# elektrosluch.net
KiCad netlist of a schematic drawn in EAGLE
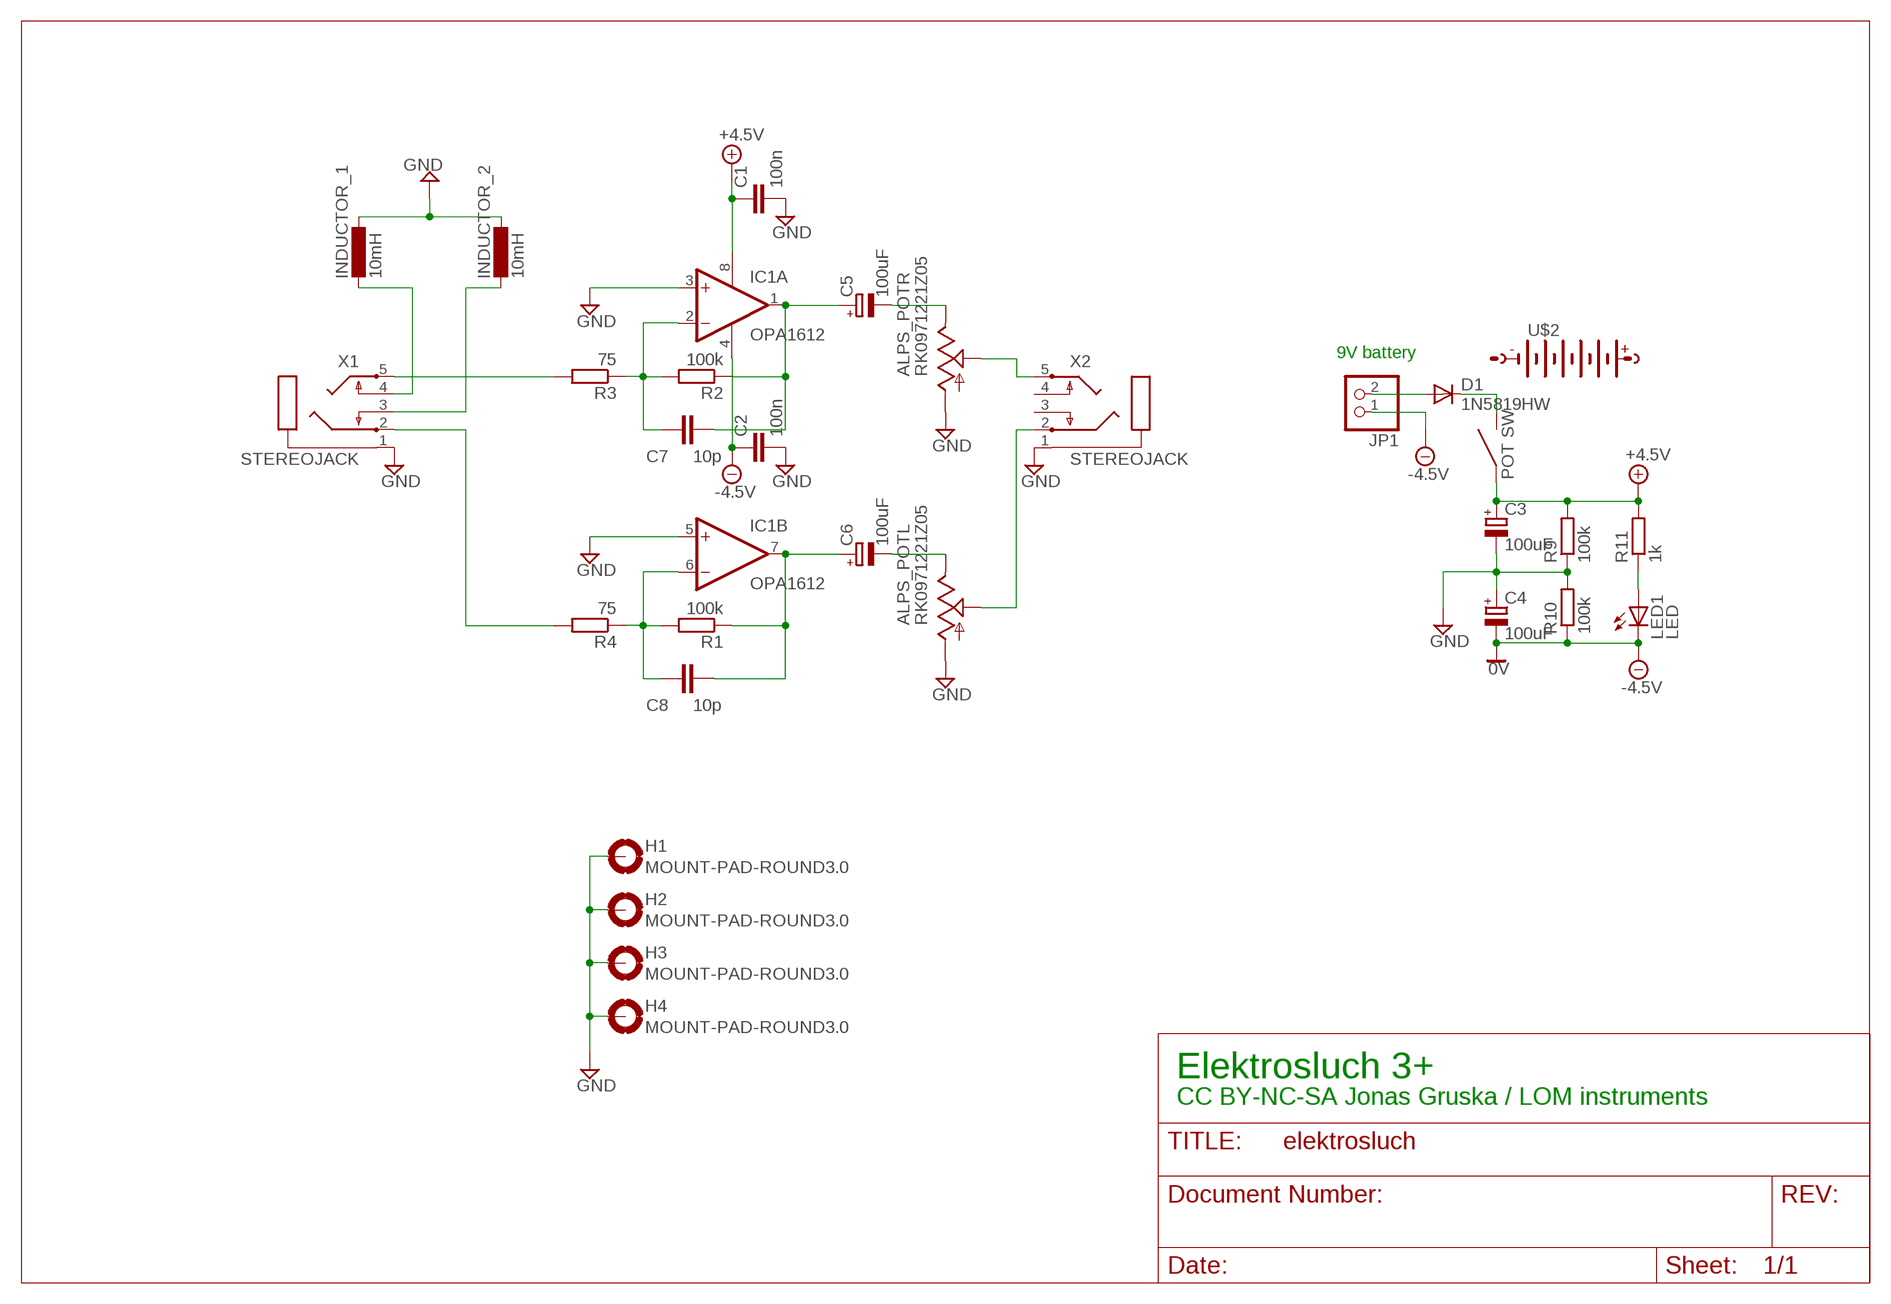
[diagram p0: schematic, sheet 1]

(export (version "E")
  (design (tool "Eeschema 10.0.6"))
  (components
    (comp (ref "ALPS_POT")
      (value "RK0971221Z05")
      (footprint "eagle-import:ALPS_RK0971221Z0X")
      (libsource (lib "eagle-import") (part "ALPS_RK0971221Z0N"))
    )
    (comp (ref "C1")
      (value "100n")
      (footprint "eagle-import:C0603")
      (libsource (lib "eagle-import") (part "C-EUC0603"))
    )
    (comp (ref "C2")
      (value "100n")
      (footprint "eagle-import:C0603")
      (libsource (lib "eagle-import") (part "C-EUC0603"))
    )
    (comp (ref "C3")
      (value "100uF")
      (footprint "eagle-import:UD-6,3X5,8_NICHICON")
      (libsource (lib "eagle-import") (part "CPOL-EUUD-6,3X8,8"))
    )
    (comp (ref "C4")
      (value "100uF")
      (footprint "eagle-import:UD-6,3X5,8_NICHICON")
      (libsource (lib "eagle-import") (part "CPOL-EUUD-6,3X8,8"))
    )
    (comp (ref "C5")
      (value "100uF")
      (footprint "eagle-import:UD-6,3X5,8_NICHICON")
      (libsource (lib "eagle-import") (part "CPOL-EUUD-6,3X8,8"))
    )
    (comp (ref "C6")
      (value "100uF")
      (footprint "eagle-import:UD-6,3X5,8_NICHICON")
      (libsource (lib "eagle-import") (part "CPOL-EUUD-6,3X8,8"))
    )
    (comp (ref "C7")
      (value "10p")
      (footprint "eagle-import:C0603")
      (libsource (lib "eagle-import") (part "C-EUC0603"))
    )
    (comp (ref "C8")
      (value "10p")
      (footprint "eagle-import:C0603")
      (libsource (lib "eagle-import") (part "C-EUC0603"))
    )
    (comp (ref "D1")
      (value "1N5819HW")
      (footprint "eagle-import:SOD123")
      (libsource (lib "eagle-import") (part "DIODE-SOD123"))
    )
    (comp (ref "H1")
      (value "MOUNT-PAD-ROUND3.0")
      (footprint "eagle-import:3,0-PAD")
      (libsource (lib "eagle-import") (part "MOUNT-PAD-ROUND3.0"))
    )
    (comp (ref "H2")
      (value "MOUNT-PAD-ROUND3.0")
      (footprint "eagle-import:3,0-PAD")
      (libsource (lib "eagle-import") (part "MOUNT-PAD-ROUND3.0"))
    )
    (comp (ref "H3")
      (value "MOUNT-PAD-ROUND3.0")
      (footprint "eagle-import:3,0-PAD")
      (libsource (lib "eagle-import") (part "MOUNT-PAD-ROUND3.0"))
    )
    (comp (ref "H4")
      (value "MOUNT-PAD-ROUND3.0")
      (footprint "eagle-import:3,0-PAD")
      (libsource (lib "eagle-import") (part "MOUNT-PAD-ROUND3.0"))
    )
    (comp (ref "IC1")
      (value "OPA1612")
      (footprint "eagle-import:SO08")
      (libsource (lib "eagle-import") (part "OPA2UA134"))
    )
    (comp (ref "INDUCTOR_1")
      (value "10mH")
      (footprint "eagle-import:COIL")
      (libsource (lib "eagle-import") (part "COIL"))
    )
    (comp (ref "INDUCTOR_2")
      (value "10mH")
      (footprint "eagle-import:COIL")
      (libsource (lib "eagle-import") (part "COIL"))
    )
    (comp (ref "JP1")
      (value "PINHD-1X2")
      (footprint "eagle-import:1X02")
      (libsource (lib "eagle-import") (part "PINHD-1X2"))
    )
    (comp (ref "LED1")
      (value "LED")
      (footprint "eagle-import:LED3MM")
      (libsource (lib "eagle-import") (part "LED"))
    )
    (comp (ref "R1")
      (value "100k")
      (footprint "eagle-import:R0805")
      (libsource (lib "eagle-import") (part "R-EU_R0805"))
    )
    (comp (ref "R2")
      (value "100k")
      (footprint "eagle-import:R0805")
      (libsource (lib "eagle-import") (part "R-EU_R0805"))
    )
    (comp (ref "R3")
      (value "75")
      (footprint "eagle-import:R0805")
      (libsource (lib "eagle-import") (part "R-EU_R0805"))
    )
    (comp (ref "R4")
      (value "75")
      (footprint "eagle-import:R0805")
      (libsource (lib "eagle-import") (part "R-EU_R0805"))
    )
    (comp (ref "R9")
      (value "100k")
      (footprint "eagle-import:R0805")
      (libsource (lib "eagle-import") (part "R-EU_R0805"))
    )
    (comp (ref "R10")
      (value "100k")
      (footprint "eagle-import:R0805")
      (libsource (lib "eagle-import") (part "R-EU_R0805"))
    )
    (comp (ref "R11")
      (value "1k")
      (footprint "eagle-import:R0805")
      (libsource (lib "eagle-import") (part "R-EU_R0805"))
    )
    (comp (ref "U$2")
      (value "BATT")
      (footprint "eagle-import:BATT")
      (libsource (lib "eagle-import") (part "BATT"))
    )
    (comp (ref "X1")
      (value "STEREOJACK")
      (footprint "eagle-import:STX3100")
      (libsource (lib "eagle-import") (part "STEREOJACK"))
    )
    (comp (ref "X2")
      (value "STEREOJACK")
      (footprint "eagle-import:STX3100")
      (libsource (lib "eagle-import") (part "STEREOJACK"))
    )
  )
  (nets
    (net (code "1") (name "+4.5V") (class "Default")
      (node (ref "ALPS_POT") (pin "S1") (pinfunction "S1_S1") (pintype "power_in"))
      (node (ref "C1") (pin "1") (pinfunction "1_1") (pintype "passive"))
      (node (ref "C3") (pin "+") (pinfunction "+_+") (pintype "passive"))
      (node (ref "IC1") (pin "8") (pinfunction "V+_8") (pintype "power_in"))
      (node (ref "R11") (pin "2") (pinfunction "2_2") (pintype "passive"))
      (node (ref "R9") (pin "2") (pinfunction "2_2") (pintype "passive"))
    )
    (net (code "2") (name "-4.5V") (class "Default")
      (node (ref "C2") (pin "1") (pinfunction "1_1") (pintype "passive"))
      (node (ref "C4") (pin "-") (pinfunction "-_-") (pintype "passive"))
      (node (ref "IC1") (pin "4") (pinfunction "V-_4") (pintype "power_in"))
      (node (ref "JP1") (pin "1") (pinfunction "1_1") (pintype "passive"))
      (node (ref "LED1") (pin "K") (pinfunction "C_K") (pintype "passive"))
      (node (ref "R10") (pin "1") (pinfunction "1_1") (pintype "passive"))
    )
    (net (code "3") (name "GND") (class "Default")
      (node (ref "ALPS_POT") (pin "G1") (pinfunction "1_G1") (pintype "passive"))
      (node (ref "ALPS_POT") (pin "G2") (pinfunction "1_G2") (pintype "passive"))
      (node (ref "C1") (pin "2") (pinfunction "2_2") (pintype "passive"))
      (node (ref "C2") (pin "2") (pinfunction "2_2") (pintype "passive"))
      (node (ref "C3") (pin "-") (pinfunction "-_-") (pintype "passive"))
      (node (ref "C4") (pin "+") (pinfunction "+_+") (pintype "passive"))
      (node (ref "H1") (pin "B3,0") (pinfunction "MOUNT_B3,0") (pintype "passive"))
      (node (ref "H2") (pin "B3,0") (pinfunction "MOUNT_B3,0") (pintype "passive"))
      (node (ref "H3") (pin "B3,0") (pinfunction "MOUNT_B3,0") (pintype "passive"))
      (node (ref "H4") (pin "B3,0") (pinfunction "MOUNT_B3,0") (pintype "passive"))
      (node (ref "IC1") (pin "3") (pinfunction "+IN_3") (pintype "input"))
      (node (ref "IC1") (pin "5") (pinfunction "+IN_5") (pintype "input"))
      (node (ref "INDUCTOR_1") (pin "P$1") (pinfunction "1_P$1") (pintype "passive"))
      (node (ref "INDUCTOR_2") (pin "P$1") (pinfunction "1_P$1") (pintype "passive"))
      (node (ref "R10") (pin "2") (pinfunction "2_2") (pintype "passive"))
      (node (ref "R9") (pin "1") (pinfunction "1_1") (pintype "passive"))
      (node (ref "X1") (pin "1") (pinfunction "1_1") (pintype "passive"))
      (node (ref "X2") (pin "1") (pinfunction "1_1") (pintype "passive"))
    )
    (net (code "4") (name "Net-(ALPS_POT-PadS2)") (class "Default")
      (node (ref "ALPS_POT") (pin "S2") (pinfunction "S2_S2") (pintype "power_in"))
      (node (ref "D1") (pin "C") (pinfunction "C_C") (pintype "passive"))
    )
    (net (code "5") (name "Net-(ALPS_POTB-2)") (class "Default")
      (node (ref "ALPS_POT") (pin "O1") (pinfunction "2_O1") (pintype "passive"))
      (node (ref "X2") (pin "2") (pinfunction "2_2") (pintype "passive"))
    )
    (net (code "6") (name "Net-(ALPS_POTB-3)") (class "Default")
      (node (ref "ALPS_POT") (pin "I1") (pinfunction "3_I1") (pintype "passive"))
      (node (ref "C6") (pin "-") (pinfunction "-_-") (pintype "passive"))
    )
    (net (code "7") (name "Net-(ALPS_POTC-2)") (class "Default")
      (node (ref "ALPS_POT") (pin "O2") (pinfunction "2_O2") (pintype "passive"))
      (node (ref "X2") (pin "5") (pinfunction "5_5") (pintype "passive"))
    )
    (net (code "8") (name "Net-(ALPS_POTC-3)") (class "Default")
      (node (ref "ALPS_POT") (pin "I2") (pinfunction "3_I2") (pintype "passive"))
      (node (ref "C5") (pin "-") (pinfunction "-_-") (pintype "passive"))
    )
    (net (code "9") (name "Net-(D1-PadA)") (class "Default")
      (node (ref "D1") (pin "A") (pinfunction "A_A") (pintype "passive"))
      (node (ref "JP1") (pin "2") (pinfunction "2_2") (pintype "passive"))
    )
    (net (code "10") (name "Net-(IC1A--IN)") (class "Default")
      (node (ref "C7") (pin "1") (pinfunction "1_1") (pintype "passive"))
      (node (ref "IC1") (pin "2") (pinfunction "-IN_2") (pintype "input"))
      (node (ref "R2") (pin "2") (pinfunction "2_2") (pintype "passive"))
      (node (ref "R3") (pin "1") (pinfunction "1_1") (pintype "passive"))
    )
    (net (code "11") (name "Net-(IC1A-OUT)") (class "Default")
      (node (ref "C5") (pin "+") (pinfunction "+_+") (pintype "passive"))
      (node (ref "C7") (pin "2") (pinfunction "2_2") (pintype "passive"))
      (node (ref "IC1") (pin "1") (pinfunction "OUT_1") (pintype "output"))
      (node (ref "R2") (pin "1") (pinfunction "1_1") (pintype "passive"))
    )
    (net (code "12") (name "Net-(IC1B--IN)") (class "Default")
      (node (ref "C8") (pin "1") (pinfunction "1_1") (pintype "passive"))
      (node (ref "IC1") (pin "6") (pinfunction "-IN_6") (pintype "input"))
      (node (ref "R1") (pin "2") (pinfunction "2_2") (pintype "passive"))
      (node (ref "R4") (pin "1") (pinfunction "1_1") (pintype "passive"))
    )
    (net (code "13") (name "Net-(IC1B-OUT)") (class "Default")
      (node (ref "C6") (pin "+") (pinfunction "+_+") (pintype "passive"))
      (node (ref "C8") (pin "2") (pinfunction "2_2") (pintype "passive"))
      (node (ref "IC1") (pin "7") (pinfunction "OUT_7") (pintype "output"))
      (node (ref "R1") (pin "1") (pinfunction "1_1") (pintype "passive"))
    )
    (net (code "14") (name "Net-(INDUCTOR_1-2)") (class "Default")
      (node (ref "INDUCTOR_1") (pin "P$2") (pinfunction "2_P$2") (pintype "passive"))
      (node (ref "X1") (pin "4") (pinfunction "4_4") (pintype "passive"))
    )
    (net (code "15") (name "Net-(INDUCTOR_2-2)") (class "Default")
      (node (ref "INDUCTOR_2") (pin "P$2") (pinfunction "2_P$2") (pintype "passive"))
      (node (ref "X1") (pin "3") (pinfunction "3_3") (pintype "passive"))
    )
    (net (code "16") (name "Net-(LED1-PadA)") (class "Default")
      (node (ref "LED1") (pin "A") (pinfunction "A_A") (pintype "passive"))
      (node (ref "R11") (pin "1") (pinfunction "1_1") (pintype "passive"))
    )
    (net (code "17") (name "Net-(R3-Pad2)") (class "Default")
      (node (ref "R3") (pin "2") (pinfunction "2_2") (pintype "passive"))
      (node (ref "X1") (pin "5") (pinfunction "5_5") (pintype "passive"))
    )
    (net (code "18") (name "Net-(R4-Pad2)") (class "Default")
      (node (ref "R4") (pin "2") (pinfunction "2_2") (pintype "passive"))
      (node (ref "X1") (pin "2") (pinfunction "2_2") (pintype "passive"))
    )
    (net (code "19") (name "unconnected-(X2-Pad3)") (class "Default")
      (node (ref "X2") (pin "3") (pinfunction "3_3") (pintype "passive"))
    )
    (net (code "20") (name "unconnected-(X2-Pad4)") (class "Default")
      (node (ref "X2") (pin "4") (pinfunction "4_4") (pintype "passive"))
    )
  )
)
